# nRF51822.net
KiCad netlist of a schematic drawn in Altium Designer
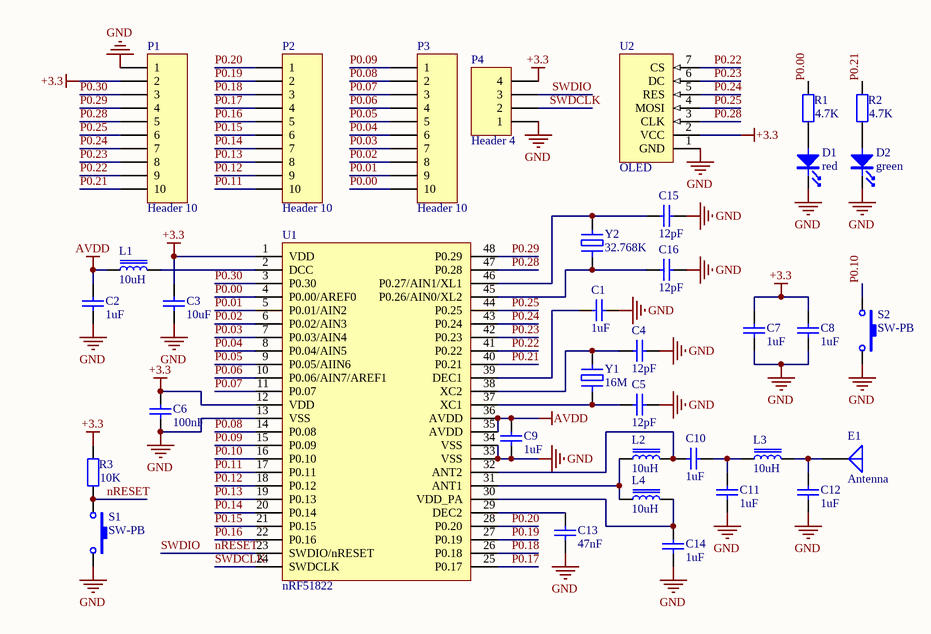
[diagram p0: nRF51822.SchDoc]

(export (version "E")
  (design (tool "Eeschema 10.0.6"))
  (components
    (comp (ref "C1")
      (value "1uF")
      (footprint "电容_C0603")
      (fields (field (name "C") "1uF"))
      (libsource (lib "元件库") (part "cap"))
    )
    (comp (ref "C2")
      (value "1uF")
      (footprint "电容_C0603")
      (fields (field (name "C") "1uF"))
      (libsource (lib "元件库") (part "cap"))
    )
    (comp (ref "C3")
      (value "10uF")
      (footprint "电容_C0603")
      (fields (field (name "C") "10uF"))
      (libsource (lib "元件库") (part "cap"))
    )
    (comp (ref "C4")
      (value "12pF")
      (footprint "电容_C0603")
      (fields (field (name "C") "12pF"))
      (libsource (lib "元件库") (part "cap"))
    )
    (comp (ref "C5")
      (value "12pF")
      (footprint "电容_C0603")
      (fields (field (name "C") "12pF"))
      (libsource (lib "元件库") (part "cap"))
    )
    (comp (ref "C6")
      (value "100nF")
      (footprint "电容_C0603")
      (fields (field (name "C") "100nF"))
      (libsource (lib "元件库") (part "cap"))
    )
    (comp (ref "C7")
      (value "1uF")
      (footprint "电容_C0603")
      (fields (field (name "C") "1uF"))
      (libsource (lib "元件库") (part "cap"))
    )
    (comp (ref "C8")
      (value "1uF")
      (footprint "电容_C0603")
      (fields (field (name "C") "1uF"))
      (libsource (lib "元件库") (part "cap"))
    )
    (comp (ref "C9")
      (value "1uF")
      (footprint "电容_C0603")
      (fields (field (name "C") "1uF"))
      (libsource (lib "元件库") (part "cap"))
    )
    (comp (ref "C10")
      (value "1uF")
      (footprint "电容_C0603")
      (fields (field (name "C") "1uF"))
      (libsource (lib "元件库") (part "cap"))
    )
    (comp (ref "C11")
      (value "1uF")
      (footprint "电容_C0603")
      (fields (field (name "C") "1uF"))
      (libsource (lib "元件库") (part "cap"))
    )
    (comp (ref "C12")
      (value "1uF")
      (footprint "电容_C0603")
      (fields (field (name "C") "1uF"))
      (libsource (lib "元件库") (part "cap"))
    )
    (comp (ref "C13")
      (value "47nF")
      (footprint "电容_C0603")
      (fields (field (name "C") "47nF"))
      (libsource (lib "元件库") (part "cap"))
    )
    (comp (ref "C14")
      (value "1uF")
      (footprint "电容_C0603")
      (fields (field (name "C") "1uF"))
      (libsource (lib "元件库") (part "cap"))
    )
    (comp (ref "C15")
      (value "12pF")
      (footprint "电容_C0603")
      (fields (field (name "C") "12pF"))
      (libsource (lib "元件库") (part "cap"))
    )
    (comp (ref "C16")
      (value "12pF")
      (footprint "电容_C0603")
      (fields (field (name "C") "12pF"))
      (libsource (lib "元件库") (part "cap"))
    )
    (comp (ref "D1") (value "red") (footprint "LED_0603") (libsource (lib "元件库") (part "LED")))
    (comp (ref "D2") (value "green") (footprint "LED_0603") (libsource (lib "元件库") (part "LED")))
    (comp (ref "E1")
      (value "Antenna")
      (footprint "AN9520")
      (description "Generic Antenna")
      (fields (field (name "PUBLISHER") "Altium Limited"))
      (libsource (lib "我的元件库") (part "Antenna"))
    )
    (comp (ref "L1")
      (value "10uH")
      (footprint "变压器电感_0420")
      (fields (field (name "_VALUE") "10uH"))
      (libsource (lib "元件库") (part "Inductor Iron 2"))
    )
    (comp (ref "L2")
      (value "10uH")
      (footprint "电阻_R0603")
      (fields (field (name "_VALUE") "10uH"))
      (libsource (lib "元件库") (part "Inductor Iron 2"))
    )
    (comp (ref "L3")
      (value "10uH")
      (footprint "电阻_R0603")
      (fields (field (name "_VALUE") "10uH"))
      (libsource (lib "元件库") (part "Inductor Iron 2"))
    )
    (comp (ref "L4")
      (value "10uH")
      (footprint "电阻_R0603")
      (fields (field (name "_VALUE") "10uH"))
      (libsource (lib "元件库") (part "Inductor Iron 2"))
    )
    (comp (ref "P1")
      (value "Header 10")
      (footprint "HDR1X10")
      (description "Header, 10-Pin")
      (fields (field (name "PUBLISHER") "Altium Limited"))
      (libsource (lib "Miscellaneous Connectors") (part "Header 10"))
    )
    (comp (ref "P2")
      (value "Header 10")
      (footprint "HDR1X10")
      (description "Header, 10-Pin")
      (fields (field (name "PUBLISHER") "Altium Limited"))
      (libsource (lib "Miscellaneous Connectors") (part "Header 10"))
    )
    (comp (ref "P3")
      (value "Header 10")
      (footprint "HDR1X10")
      (description "Header, 10-Pin")
      (fields (field (name "PUBLISHER") "Altium Limited"))
      (libsource (lib "Miscellaneous Connectors") (part "Header 10"))
    )
    (comp (ref "P4")
      (value "Header 4")
      (footprint "HDR1X4")
      (description "Header, 4-Pin")
      (fields (field (name "PUBLISHER") "Altium Limited"))
      (libsource (lib "Miscellaneous Connectors") (part "Header 4"))
    )
    (comp (ref "R1")
      (value "4.7K")
      (footprint "电阻_R0603")
      (description "Resistor")
      (fields (field (name "Comment") "Res2") (field (name "PUBLISHER") "Altium Limited"))
      (libsource (lib "Miscellaneous Devices") (part "Res2"))
    )
    (comp (ref "R2")
      (value "4.7K")
      (footprint "电阻_R0603")
      (description "Resistor")
      (fields (field (name "Comment") "Res2") (field (name "PUBLISHER") "Altium Limited"))
      (libsource (lib "Miscellaneous Devices") (part "Res2"))
    )
    (comp (ref "R3")
      (value "10K")
      (footprint "电阻_R0603")
      (description "Resistor")
      (fields (field (name "Comment") "Res2") (field (name "PUBLISHER") "Altium Limited"))
      (libsource (lib "Miscellaneous Devices") (part "Res2"))
    )
    (comp (ref "S1")
      (value "SW-PB")
      (footprint "SPST4")
      (description "Switch")
      (fields (field (name "PUBLISHER") "Altium Limited"))
      (libsource (lib "我的元件库") (part "SW-PB"))
    )
    (comp (ref "S2")
      (value "SW-PB")
      (footprint "SPST4")
      (description "Switch")
      (fields (field (name "PUBLISHER") "Altium Limited"))
      (libsource (lib "我的元件库") (part "SW-PB"))
    )
    (comp (ref "U1")
      (value "nRF51822")
      (footprint "QFN48 6X6 mm")
      (description "Multiprotocol Bluetooth® 4.0 low energy/2.4 GHz RF SoC")
      (libsource (lib "我的元件库") (part "nRF51822"))
    )
    (comp (ref "U2")
      (value "OLED")
      (footprint "OLED 0.96")
      (description "1.3寸或0.96寸SPI接口的OLED")
      (libsource (lib "我的元件库") (part "OLED_SPI"))
    )
    (comp (ref "Y1")
      (value "XTAL")
      (footprint "晶振_2016")
      (fields (field (name "F") "16M"))
      (libsource (lib "元件库") (part "XTAL"))
    )
    (comp (ref "Y2")
      (value "32.768K")
      (footprint "晶振_3215")
      (fields (field (name "_FREQUENCY") "32.768K"))
      (libsource (lib "TriggersLib") (part "XTAL_A"))
    )
  )
  (nets
    (net (code "1") (name "+3.3") (class "Default")
      (node (ref "C3") (pin "2") (pinfunction "2_2") (pintype "passive"))
      (node (ref "C6") (pin "1") (pinfunction "1_1") (pintype "passive"))
      (node (ref "C7") (pin "2") (pinfunction "2_2") (pintype "passive"))
      (node (ref "C8") (pin "2") (pinfunction "2_2") (pintype "passive"))
      (node (ref "P1") (pin "2") (pinfunction "2_2") (pintype "passive"))
      (node (ref "P4") (pin "4") (pinfunction "4_4") (pintype "passive"))
      (node (ref "R3") (pin "1") (pinfunction "1_1") (pintype "passive"))
      (node (ref "U1") (pin "1") (pinfunction "VDD_1") (pintype "passive"))
      (node (ref "U1") (pin "12") (pinfunction "VDD_12") (pintype "passive"))
      (node (ref "U2") (pin "2") (pinfunction "VCC_2") (pintype "power_in"))
    )
    (net (code "2") (name "/P0.00") (class "Default")
      (node (ref "P3") (pin "10") (pinfunction "10_10") (pintype "passive"))
      (node (ref "R1") (pin "1") (pinfunction "1_1") (pintype "passive"))
      (node (ref "U1") (pin "4") (pinfunction "P0.00/AREF0_4") (pintype "passive"))
    )
    (net (code "3") (name "/P0.01") (class "Default")
      (node (ref "P3") (pin "9") (pinfunction "9_9") (pintype "passive"))
      (node (ref "U1") (pin "5") (pinfunction "P0.01/AIN2_5") (pintype "passive"))
    )
    (net (code "4") (name "/P0.02") (class "Default")
      (node (ref "P3") (pin "8") (pinfunction "8_8") (pintype "passive"))
      (node (ref "U1") (pin "6") (pinfunction "P0.02/AIN3_6") (pintype "passive"))
    )
    (net (code "5") (name "/P0.03") (class "Default")
      (node (ref "P3") (pin "7") (pinfunction "7_7") (pintype "passive"))
      (node (ref "U1") (pin "7") (pinfunction "P0.03/AIN4_7") (pintype "passive"))
    )
    (net (code "6") (name "/P0.04") (class "Default")
      (node (ref "P3") (pin "6") (pinfunction "6_6") (pintype "passive"))
      (node (ref "U1") (pin "8") (pinfunction "P0.04/AIN5_8") (pintype "passive"))
    )
    (net (code "7") (name "/P0.05") (class "Default")
      (node (ref "P3") (pin "5") (pinfunction "5_5") (pintype "passive"))
      (node (ref "U1") (pin "9") (pinfunction "P0.05/AIIN6_9") (pintype "passive"))
    )
    (net (code "8") (name "/P0.06") (class "Default")
      (node (ref "P3") (pin "4") (pinfunction "4_4") (pintype "passive"))
      (node (ref "U1") (pin "10") (pinfunction "P0.06/AIN7/AREF1_10") (pintype "passive"))
    )
    (net (code "9") (name "/P0.07") (class "Default")
      (node (ref "P3") (pin "3") (pinfunction "3_3") (pintype "passive"))
      (node (ref "U1") (pin "11") (pinfunction "P0.07_11") (pintype "passive"))
    )
    (net (code "10") (name "/P0.08") (class "Default")
      (node (ref "P3") (pin "2") (pinfunction "2_2") (pintype "passive"))
      (node (ref "U1") (pin "14") (pinfunction "P0.08_14") (pintype "passive"))
    )
    (net (code "11") (name "/P0.09") (class "Default")
      (node (ref "P3") (pin "1") (pinfunction "1_1") (pintype "passive"))
      (node (ref "U1") (pin "15") (pinfunction "P0.09_15") (pintype "passive"))
    )
    (net (code "12") (name "/P0.10") (class "Default")
      (node (ref "S2") (pin "1") (pinfunction "1_1") (pintype "passive"))
      (node (ref "U1") (pin "16") (pinfunction "P0.10_16") (pintype "passive"))
    )
    (net (code "13") (name "/P0.11") (class "Default")
      (node (ref "P2") (pin "10") (pinfunction "10_10") (pintype "passive"))
      (node (ref "U1") (pin "17") (pinfunction "P0.11_17") (pintype "passive"))
    )
    (net (code "14") (name "/P0.12") (class "Default")
      (node (ref "P2") (pin "9") (pinfunction "9_9") (pintype "passive"))
      (node (ref "U1") (pin "18") (pinfunction "P0.12_18") (pintype "passive"))
    )
    (net (code "15") (name "/P0.13") (class "Default")
      (node (ref "P2") (pin "8") (pinfunction "8_8") (pintype "passive"))
      (node (ref "U1") (pin "19") (pinfunction "P0.13_19") (pintype "passive"))
    )
    (net (code "16") (name "/P0.14") (class "Default")
      (node (ref "P2") (pin "7") (pinfunction "7_7") (pintype "passive"))
      (node (ref "U1") (pin "20") (pinfunction "P0.14_20") (pintype "passive"))
    )
    (net (code "17") (name "/P0.15") (class "Default")
      (node (ref "P2") (pin "6") (pinfunction "6_6") (pintype "passive"))
      (node (ref "U1") (pin "21") (pinfunction "P0.15_21") (pintype "passive"))
    )
    (net (code "18") (name "/P0.16") (class "Default")
      (node (ref "P2") (pin "5") (pinfunction "5_5") (pintype "passive"))
      (node (ref "U1") (pin "22") (pinfunction "P0.16_22") (pintype "passive"))
    )
    (net (code "19") (name "/P0.17") (class "Default")
      (node (ref "P2") (pin "4") (pinfunction "4_4") (pintype "passive"))
      (node (ref "U1") (pin "25") (pinfunction "P0.17_25") (pintype "passive"))
    )
    (net (code "20") (name "/P0.18") (class "Default")
      (node (ref "P2") (pin "3") (pinfunction "3_3") (pintype "passive"))
      (node (ref "U1") (pin "26") (pinfunction "P0.18_26") (pintype "passive"))
    )
    (net (code "21") (name "/P0.19") (class "Default")
      (node (ref "P2") (pin "2") (pinfunction "2_2") (pintype "passive"))
      (node (ref "U1") (pin "27") (pinfunction "P0.19_27") (pintype "passive"))
    )
    (net (code "22") (name "/P0.20") (class "Default")
      (node (ref "P2") (pin "1") (pinfunction "1_1") (pintype "passive"))
      (node (ref "U1") (pin "28") (pinfunction "P0.20_28") (pintype "passive"))
    )
    (net (code "23") (name "/P0.21") (class "Default")
      (node (ref "P1") (pin "10") (pinfunction "10_10") (pintype "passive"))
      (node (ref "R2") (pin "1") (pinfunction "1_1") (pintype "passive"))
      (node (ref "U1") (pin "40") (pinfunction "P0.21_40") (pintype "passive"))
    )
    (net (code "24") (name "/P0.22") (class "Default")
      (node (ref "P1") (pin "9") (pinfunction "9_9") (pintype "passive"))
      (node (ref "U1") (pin "41") (pinfunction "P0.22_41") (pintype "passive"))
      (node (ref "U2") (pin "7") (pinfunction "CS_7") (pintype "input"))
    )
    (net (code "25") (name "/P0.23") (class "Default")
      (node (ref "P1") (pin "8") (pinfunction "8_8") (pintype "passive"))
      (node (ref "U1") (pin "42") (pinfunction "P0.23_42") (pintype "passive"))
      (node (ref "U2") (pin "6") (pinfunction "DC_6") (pintype "input"))
    )
    (net (code "26") (name "/P0.24") (class "Default")
      (node (ref "P1") (pin "7") (pinfunction "7_7") (pintype "passive"))
      (node (ref "U1") (pin "43") (pinfunction "P0.24_43") (pintype "passive"))
      (node (ref "U2") (pin "5") (pinfunction "RES_5") (pintype "input"))
    )
    (net (code "27") (name "/P0.25") (class "Default")
      (node (ref "P1") (pin "6") (pinfunction "6_6") (pintype "passive"))
      (node (ref "U1") (pin "44") (pinfunction "P0.25_44") (pintype "passive"))
      (node (ref "U2") (pin "4") (pinfunction "MOSI_4") (pintype "input"))
    )
    (net (code "28") (name "/P0.28") (class "Default")
      (node (ref "P1") (pin "5") (pinfunction "5_5") (pintype "passive"))
      (node (ref "U1") (pin "47") (pinfunction "P0.28_47") (pintype "passive"))
      (node (ref "U2") (pin "3") (pinfunction "CLK_3") (pintype "input"))
    )
    (net (code "29") (name "/P0.29") (class "Default")
      (node (ref "P1") (pin "4") (pinfunction "4_4") (pintype "passive"))
      (node (ref "U1") (pin "48") (pinfunction "P0.29_48") (pintype "passive"))
    )
    (net (code "30") (name "/P0.30") (class "Default")
      (node (ref "P1") (pin "3") (pinfunction "3_3") (pintype "passive"))
      (node (ref "U1") (pin "3") (pinfunction "P0.30_3") (pintype "passive"))
    )
    (net (code "31") (name "/SWDCLK") (class "Default")
      (node (ref "P4") (pin "2") (pinfunction "2_2") (pintype "passive"))
      (node (ref "U1") (pin "24") (pinfunction "SWDCLK_24") (pintype "passive"))
    )
    (net (code "32") (name "/SWDIO") (class "Default")
      (node (ref "P4") (pin "3") (pinfunction "3_3") (pintype "passive"))
      (node (ref "R3") (pin "2") (pinfunction "2_2") (pintype "passive"))
      (node (ref "S1") (pin "1") (pinfunction "1_1") (pintype "passive"))
      (node (ref "U1") (pin "23") (pinfunction "SWDIO/nRESET_23") (pintype "passive"))
    )
    (net (code "33") (name "AVDD") (class "Default")
      (node (ref "C2") (pin "2") (pinfunction "2_2") (pintype "passive"))
      (node (ref "C9") (pin "1") (pinfunction "1_1") (pintype "passive"))
      (node (ref "L1") (pin "1") (pinfunction "1_1") (pintype "passive"))
      (node (ref "U1") (pin "35") (pinfunction "AVDD_35") (pintype "passive"))
      (node (ref "U1") (pin "36") (pinfunction "AVDD_36") (pintype "passive"))
    )
    (net (code "34") (name "GND") (class "Default")
      (node (ref "C1") (pin "1") (pinfunction "1_1") (pintype "passive"))
      (node (ref "C11") (pin "2") (pinfunction "2_2") (pintype "passive"))
      (node (ref "C12") (pin "2") (pinfunction "2_2") (pintype "passive"))
      (node (ref "C13") (pin "1") (pinfunction "1_1") (pintype "passive"))
      (node (ref "C14") (pin "1") (pinfunction "1_1") (pintype "passive"))
      (node (ref "C15") (pin "2") (pinfunction "2_2") (pintype "passive"))
      (node (ref "C16") (pin "2") (pinfunction "2_2") (pintype "passive"))
      (node (ref "C2") (pin "1") (pinfunction "1_1") (pintype "passive"))
      (node (ref "C3") (pin "1") (pinfunction "1_1") (pintype "passive"))
      (node (ref "C4") (pin "2") (pinfunction "2_2") (pintype "passive"))
      (node (ref "C5") (pin "2") (pinfunction "2_2") (pintype "passive"))
      (node (ref "C6") (pin "2") (pinfunction "2_2") (pintype "passive"))
      (node (ref "C7") (pin "1") (pinfunction "1_1") (pintype "passive"))
      (node (ref "C8") (pin "1") (pinfunction "1_1") (pintype "passive"))
      (node (ref "C9") (pin "2") (pinfunction "2_2") (pintype "passive"))
      (node (ref "D1") (pin "K") (pinfunction "K_K") (pintype "passive"))
      (node (ref "D2") (pin "K") (pinfunction "K_K") (pintype "passive"))
      (node (ref "P1") (pin "1") (pinfunction "1_1") (pintype "passive"))
      (node (ref "P4") (pin "1") (pinfunction "1_1") (pintype "passive"))
      (node (ref "S1") (pin "2") (pinfunction "2_2") (pintype "passive"))
      (node (ref "S2") (pin "2") (pinfunction "2_2") (pintype "passive"))
      (node (ref "U1") (pin "13") (pinfunction "VSS_13") (pintype "passive"))
      (node (ref "U1") (pin "33") (pinfunction "VSS_33") (pintype "passive"))
      (node (ref "U1") (pin "34") (pinfunction "VSS_34") (pintype "passive"))
      (node (ref "U2") (pin "1") (pinfunction "GND_1") (pintype "power_in"))
    )
    (net (code "35") (name "Net-(C10-Pad1)") (class "Default")
      (node (ref "C10") (pin "1") (pinfunction "1_1") (pintype "passive"))
      (node (ref "C11") (pin "1") (pinfunction "1_1") (pintype "passive"))
      (node (ref "L3") (pin "1") (pinfunction "1_1") (pintype "passive"))
    )
    (net (code "36") (name "Net-(D1-PadA)") (class "Default")
      (node (ref "D1") (pin "A") (pinfunction "A_A") (pintype "passive"))
      (node (ref "R1") (pin "2") (pinfunction "2_2") (pintype "passive"))
    )
    (net (code "37") (name "Net-(D2-PadA)") (class "Default")
      (node (ref "D2") (pin "A") (pinfunction "A_A") (pintype "passive"))
      (node (ref "R2") (pin "2") (pinfunction "2_2") (pintype "passive"))
    )
    (net (code "38") (name "Net-(E1-A)") (class "Default")
      (node (ref "C12") (pin "1") (pinfunction "1_1") (pintype "passive"))
      (node (ref "E1") (pin "1") (pinfunction "A_1") (pintype "passive"))
      (node (ref "L3") (pin "2") (pinfunction "2_2") (pintype "passive"))
    )
    (net (code "39") (name "Net-(U1-ANT1)") (class "Default")
      (node (ref "L2") (pin "1") (pinfunction "1_1") (pintype "passive"))
      (node (ref "L4") (pin "1") (pinfunction "1_1") (pintype "passive"))
      (node (ref "U1") (pin "31") (pinfunction "ANT1_31") (pintype "passive"))
    )
    (net (code "40") (name "Net-(U1-ANT2)") (class "Default")
      (node (ref "C10") (pin "2") (pinfunction "2_2") (pintype "passive"))
      (node (ref "L2") (pin "2") (pinfunction "2_2") (pintype "passive"))
      (node (ref "U1") (pin "32") (pinfunction "ANT2_32") (pintype "passive"))
    )
    (net (code "41") (name "Net-(U1-DCC)") (class "Default")
      (node (ref "L1") (pin "2") (pinfunction "2_2") (pintype "passive"))
      (node (ref "U1") (pin "2") (pinfunction "DCC_2") (pintype "passive"))
    )
    (net (code "42") (name "Net-(U1-DEC1)") (class "Default")
      (node (ref "C1") (pin "2") (pinfunction "2_2") (pintype "passive"))
      (node (ref "U1") (pin "39") (pinfunction "DEC1_39") (pintype "passive"))
    )
    (net (code "43") (name "Net-(U1-DEC2)") (class "Default")
      (node (ref "C13") (pin "2") (pinfunction "2_2") (pintype "passive"))
      (node (ref "U1") (pin "29") (pinfunction "DEC2_29") (pintype "passive"))
    )
    (net (code "44") (name "Net-(U1-P0.26{slash}AIN0{slash}XL2)") (class "Default")
      (node (ref "C16") (pin "1") (pinfunction "1_1") (pintype "passive"))
      (node (ref "U1") (pin "45") (pinfunction "P0.26/AIN0/XL2_45") (pintype "passive"))
      (node (ref "Y2") (pin "1") (pinfunction "1_1") (pintype "passive"))
    )
    (net (code "45") (name "Net-(U1-P0.27{slash}AIN1{slash}XL1)") (class "Default")
      (node (ref "C15") (pin "1") (pinfunction "1_1") (pintype "passive"))
      (node (ref "U1") (pin "46") (pinfunction "P0.27/AIN1/XL1_46") (pintype "passive"))
      (node (ref "Y2") (pin "2") (pinfunction "2_2") (pintype "passive"))
    )
    (net (code "46") (name "Net-(U1-VDD_PA)") (class "Default")
      (node (ref "C14") (pin "2") (pinfunction "2_2") (pintype "passive"))
      (node (ref "L4") (pin "2") (pinfunction "2_2") (pintype "passive"))
      (node (ref "U1") (pin "30") (pinfunction "VDD_PA_30") (pintype "passive"))
    )
    (net (code "47") (name "Net-(U1-XC1)") (class "Default")
      (node (ref "C5") (pin "1") (pinfunction "1_1") (pintype "passive"))
      (node (ref "U1") (pin "37") (pinfunction "XC1_37") (pintype "passive"))
      (node (ref "Y1") (pin "1") (pinfunction "1_1") (pintype "passive"))
    )
    (net (code "48") (name "Net-(U1-XC2)") (class "Default")
      (node (ref "C4") (pin "1") (pinfunction "1_1") (pintype "passive"))
      (node (ref "U1") (pin "38") (pinfunction "XC2_38") (pintype "passive"))
      (node (ref "Y1") (pin "2") (pinfunction "2_2") (pintype "passive"))
    )
  )
)
